# control-board-v0_2_1.net
KiCad netlist of a schematic drawn in EAGLE
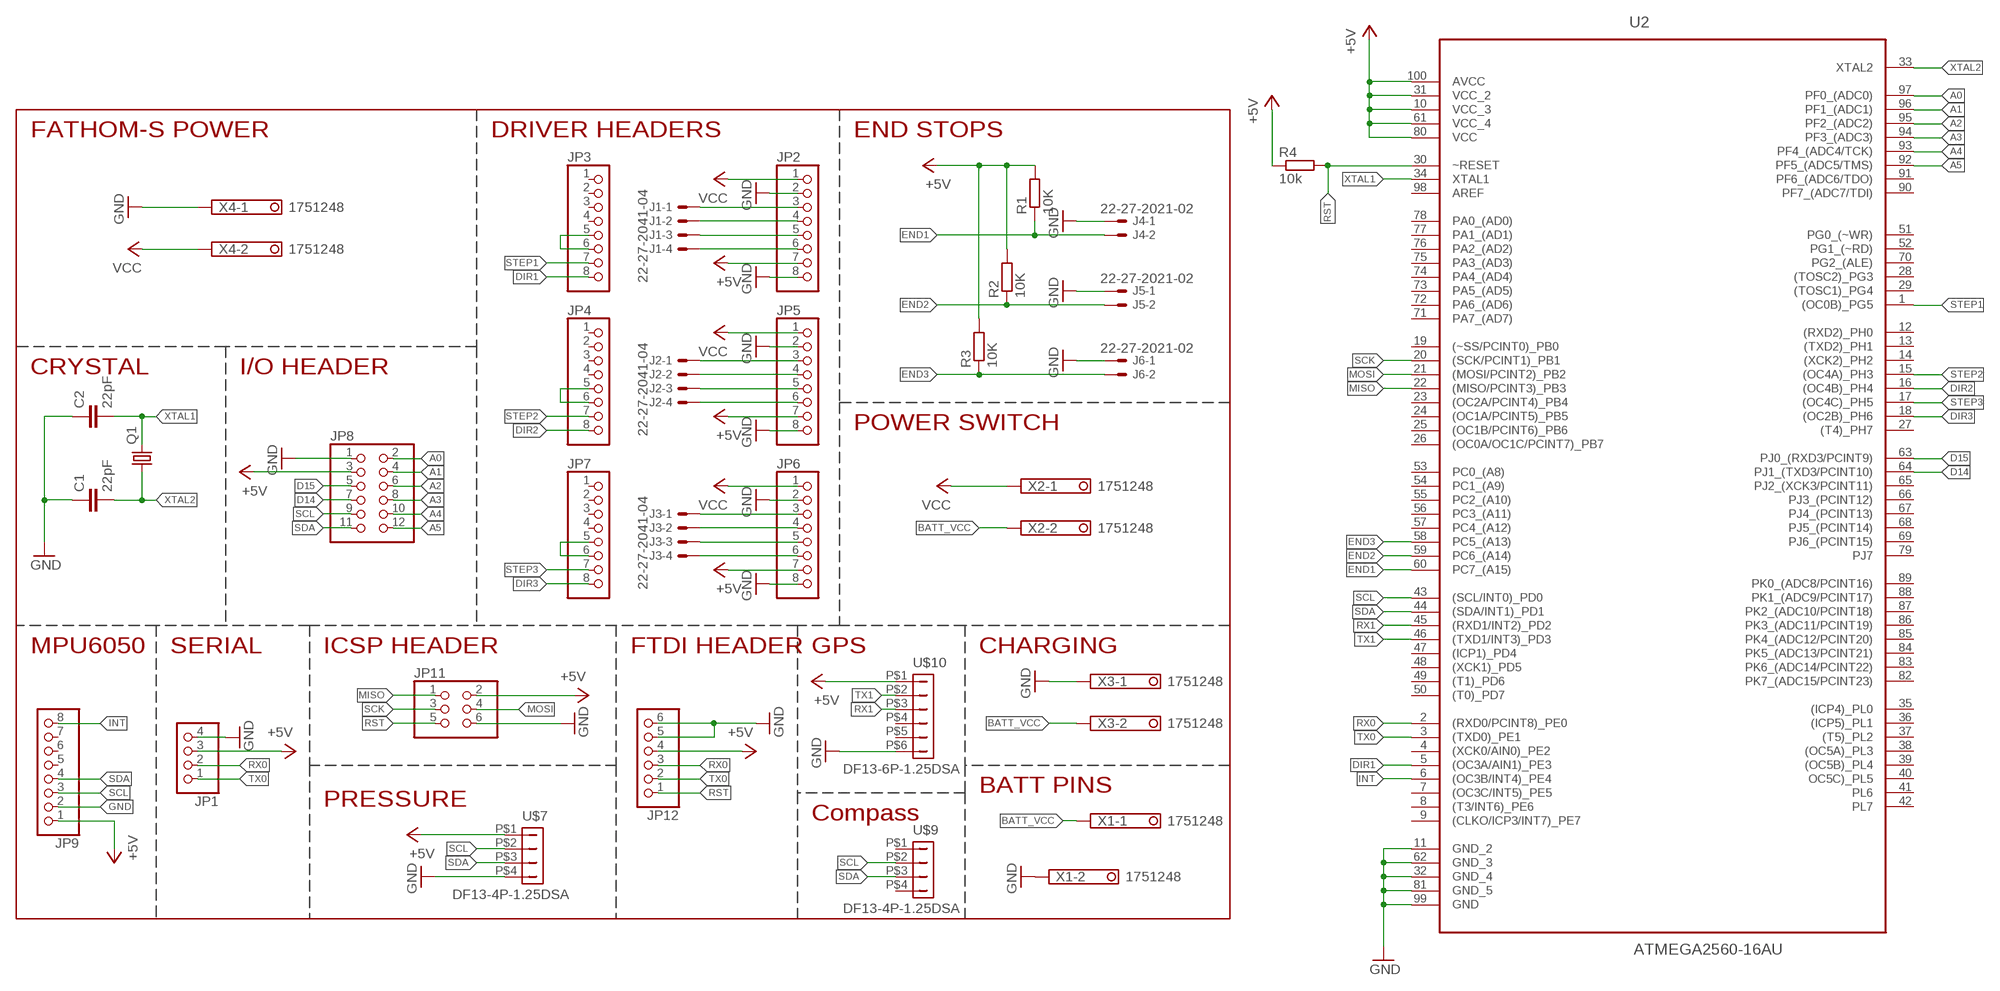
[diagram p0: schematic, sheet 1]

(export (version "E")
  (design (tool "Eeschema 10.0.6"))
  (components
    (comp (ref "C1")
      (value "22pF")
      (footprint "eagle-import:C0603")
      (libsource (lib "eagle-import") (part "C-EUC0603"))
    )
    (comp (ref "C2")
      (value "22pF")
      (footprint "eagle-import:C0603")
      (libsource (lib "eagle-import") (part "C-EUC0603"))
    )
    (comp (ref "J1")
      (value "22-27-2041-04")
      (footprint "eagle-import:6410-04")
      (libsource (lib "eagle-import") (part "22-?-0427-2041"))
    )
    (comp (ref "J2")
      (value "22-27-2041-04")
      (footprint "eagle-import:6410-04")
      (libsource (lib "eagle-import") (part "22-?-0427-2041"))
    )
    (comp (ref "J3")
      (value "22-27-2041-04")
      (footprint "eagle-import:6410-04")
      (libsource (lib "eagle-import") (part "22-?-0427-2041"))
    )
    (comp (ref "J4")
      (value "22-27-2021-02")
      (footprint "eagle-import:6410-02")
      (libsource (lib "eagle-import") (part "22-?-0227-2021"))
    )
    (comp (ref "J5")
      (value "22-27-2021-02")
      (footprint "eagle-import:6410-02")
      (libsource (lib "eagle-import") (part "22-?-0227-2021"))
    )
    (comp (ref "J6")
      (value "22-27-2021-02")
      (footprint "eagle-import:6410-02")
      (libsource (lib "eagle-import") (part "22-?-0227-2021"))
    )
    (comp (ref "JP1")
      (value "PINHD-1X4")
      (footprint "eagle-import:1X04")
      (libsource (lib "eagle-import") (part "PINHD-1X4"))
    )
    (comp (ref "JP2")
      (value "PINHD-1X8")
      (footprint "eagle-import:1X08")
      (libsource (lib "eagle-import") (part "PINHD-1X8"))
    )
    (comp (ref "JP3")
      (value "PINHD-1X8")
      (footprint "eagle-import:1X08")
      (libsource (lib "eagle-import") (part "PINHD-1X8"))
    )
    (comp (ref "JP4")
      (value "PINHD-1X8")
      (footprint "eagle-import:1X08")
      (libsource (lib "eagle-import") (part "PINHD-1X8"))
    )
    (comp (ref "JP5")
      (value "PINHD-1X8")
      (footprint "eagle-import:1X08")
      (libsource (lib "eagle-import") (part "PINHD-1X8"))
    )
    (comp (ref "JP6")
      (value "PINHD-1X8")
      (footprint "eagle-import:1X08")
      (libsource (lib "eagle-import") (part "PINHD-1X8"))
    )
    (comp (ref "JP7")
      (value "PINHD-1X8")
      (footprint "eagle-import:1X08")
      (libsource (lib "eagle-import") (part "PINHD-1X8"))
    )
    (comp (ref "JP8")
      (value "PINHD-2X6")
      (footprint "eagle-import:2X06")
      (libsource (lib "eagle-import") (part "PINHD-2X6"))
    )
    (comp (ref "JP9")
      (value "PINHD-1X8")
      (footprint "eagle-import:1X08")
      (libsource (lib "eagle-import") (part "PINHD-1X8"))
    )
    (comp (ref "JP11")
      (value "PINHD-2X3")
      (footprint "eagle-import:2X03")
      (libsource (lib "eagle-import") (part "PINHD-2X3"))
    )
    (comp (ref "JP12")
      (value "PINHD-1X6")
      (footprint "eagle-import:1X06")
      (libsource (lib "eagle-import") (part "PINHD-1X6"))
    )
    (comp (ref "Q1")
      (value "CRYSTALHC49U70")
      (footprint "eagle-import:HC49U70")
      (libsource (lib "eagle-import") (part "CRYSTALHC49U70"))
    )
    (comp (ref "R1")
      (value "10K")
      (footprint "eagle-import:R0603")
      (libsource (lib "eagle-import") (part "R-EU_R0603"))
    )
    (comp (ref "R2")
      (value "10K")
      (footprint "eagle-import:R0603")
      (libsource (lib "eagle-import") (part "R-EU_R0603"))
    )
    (comp (ref "R3")
      (value "10K")
      (footprint "eagle-import:R0603")
      (libsource (lib "eagle-import") (part "R-EU_R0603"))
    )
    (comp (ref "R4")
      (value "10k")
      (footprint "eagle-import:R0603")
      (libsource (lib "eagle-import") (part "R-EU_R0603"))
    )
    (comp (ref "U$7")
      (value "DF13-4P-1.25DSA")
      (footprint "eagle-import:DF13-4P-1.25DSA")
      (libsource (lib "eagle-import") (part "DF13-4P-1.25DSA"))
    )
    (comp (ref "U$9")
      (value "DF13-4P-1.25DSA")
      (footprint "eagle-import:DF13-4P-1.25DSA")
      (libsource (lib "eagle-import") (part "DF13-4P-1.25DSA"))
    )
    (comp (ref "U$10")
      (value "DF13-6P-1.25DSA")
      (footprint "eagle-import:DF13-6P-1.25DSA")
      (libsource (lib "eagle-import") (part "DF13-6P-1.25DSA"))
    )
    (comp (ref "U2")
      (value "ATMEGA2560-16AU")
      (footprint "eagle-import:QFP50P1600X1600X120-100N")
      (libsource (lib "eagle-import") (part "ATMEGA2560-16AU"))
    )
    (comp (ref "X1")
      (value "1751248")
      (footprint "eagle-import:1751248")
      (libsource (lib "eagle-import") (part "1751248"))
    )
    (comp (ref "X2")
      (value "1751248")
      (footprint "eagle-import:1751248")
      (libsource (lib "eagle-import") (part "1751248"))
    )
    (comp (ref "X3")
      (value "1751248")
      (footprint "eagle-import:1751248")
      (libsource (lib "eagle-import") (part "1751248"))
    )
    (comp (ref "X4")
      (value "1751248")
      (footprint "eagle-import:1751248")
      (libsource (lib "eagle-import") (part "1751248"))
    )
  )
  (nets
    (net (code "1") (name "+5V") (class "Default")
      (node (ref "JP1") (pin "3") (pinfunction "3_3") (pintype "passive"))
      (node (ref "JP11") (pin "2") (pinfunction "2_2") (pintype "passive"))
      (node (ref "JP12") (pin "4") (pinfunction "4_4") (pintype "passive"))
      (node (ref "JP2") (pin "7") (pinfunction "7_7") (pintype "passive"))
      (node (ref "JP5") (pin "7") (pinfunction "7_7") (pintype "passive"))
      (node (ref "JP6") (pin "7") (pinfunction "7_7") (pintype "passive"))
      (node (ref "JP8") (pin "3") (pinfunction "3_3") (pintype "passive"))
      (node (ref "JP9") (pin "1") (pinfunction "1_1") (pintype "passive"))
      (node (ref "R1") (pin "2") (pinfunction "2_2") (pintype "passive"))
      (node (ref "R2") (pin "2") (pinfunction "2_2") (pintype "passive"))
      (node (ref "R3") (pin "2") (pinfunction "2_2") (pintype "passive"))
      (node (ref "R4") (pin "1") (pinfunction "1_1") (pintype "passive"))
      (node (ref "U$10") (pin "P$1") (pinfunction "1_P$1") (pintype "passive"))
      (node (ref "U$7") (pin "P$1") (pinfunction "1_P$1") (pintype "passive"))
      (node (ref "U2") (pin "10") (pinfunction "VCC_3_10") (pintype "power_in"))
      (node (ref "U2") (pin "100") (pinfunction "AVCC_100") (pintype "power_in"))
      (node (ref "U2") (pin "31") (pinfunction "VCC_2_31") (pintype "power_in"))
      (node (ref "U2") (pin "61") (pinfunction "VCC_4_61") (pintype "power_in"))
      (node (ref "U2") (pin "80") (pinfunction "VCC_80") (pintype "power_in"))
    )
    (net (code "2") (name "A0") (class "Default")
      (node (ref "JP8") (pin "2") (pinfunction "2_2") (pintype "passive"))
      (node (ref "U2") (pin "97") (pinfunction "PF0_(ADC0)_97") (pintype "bidirectional"))
    )
    (net (code "3") (name "A1") (class "Default")
      (node (ref "JP8") (pin "4") (pinfunction "4_4") (pintype "passive"))
      (node (ref "U2") (pin "96") (pinfunction "PF1_(ADC1)_96") (pintype "bidirectional"))
    )
    (net (code "4") (name "A2") (class "Default")
      (node (ref "JP8") (pin "6") (pinfunction "6_6") (pintype "passive"))
      (node (ref "U2") (pin "95") (pinfunction "PF2_(ADC2)_95") (pintype "bidirectional"))
    )
    (net (code "5") (name "A3") (class "Default")
      (node (ref "JP8") (pin "8") (pinfunction "8_8") (pintype "passive"))
      (node (ref "U2") (pin "94") (pinfunction "PF3_(ADC3)_94") (pintype "bidirectional"))
    )
    (net (code "6") (name "A4") (class "Default")
      (node (ref "JP8") (pin "10") (pinfunction "10_10") (pintype "passive"))
      (node (ref "U2") (pin "93") (pinfunction "PF4_(ADC4/TCK)_93") (pintype "bidirectional"))
    )
    (net (code "7") (name "A5") (class "Default")
      (node (ref "JP8") (pin "12") (pinfunction "12_12") (pintype "passive"))
      (node (ref "U2") (pin "92") (pinfunction "PF5_(ADC5/TMS)_92") (pintype "bidirectional"))
    )
    (net (code "8") (name "BATT_VCC") (class "Default")
      (node (ref "X1") (pin "1") (pinfunction "K_1") (pintype "passive"))
      (node (ref "X2") (pin "2") (pinfunction "K_2") (pintype "passive"))
      (node (ref "X3") (pin "2") (pinfunction "K_2") (pintype "passive"))
    )
    (net (code "9") (name "D14") (class "Default")
      (node (ref "JP8") (pin "7") (pinfunction "7_7") (pintype "passive"))
      (node (ref "U2") (pin "64") (pinfunction "PJ1_(TXD3/PCINT10)_64") (pintype "bidirectional"))
    )
    (net (code "10") (name "D15") (class "Default")
      (node (ref "JP8") (pin "5") (pinfunction "5_5") (pintype "passive"))
      (node (ref "U2") (pin "63") (pinfunction "PJ0_(RXD3/PCINT9)_63") (pintype "bidirectional"))
    )
    (net (code "11") (name "DIR1") (class "Default")
      (node (ref "JP3") (pin "8") (pinfunction "8_8") (pintype "passive"))
      (node (ref "U2") (pin "5") (pinfunction "(OC3A/AIN1)_PE3_5") (pintype "bidirectional"))
    )
    (net (code "12") (name "DIR2") (class "Default")
      (node (ref "JP4") (pin "8") (pinfunction "8_8") (pintype "passive"))
      (node (ref "U2") (pin "16") (pinfunction "(OC4B)_PH4_16") (pintype "bidirectional"))
    )
    (net (code "13") (name "DIR3") (class "Default")
      (node (ref "JP7") (pin "8") (pinfunction "8_8") (pintype "passive"))
      (node (ref "U2") (pin "18") (pinfunction "(OC2B)_PH6_18") (pintype "bidirectional"))
    )
    (net (code "14") (name "END1") (class "Default")
      (node (ref "J4") (pin "2") (pinfunction "S_2") (pintype "passive"))
      (node (ref "R1") (pin "1") (pinfunction "1_1") (pintype "passive"))
      (node (ref "U2") (pin "60") (pinfunction "PC7_(A15)_60") (pintype "bidirectional"))
    )
    (net (code "15") (name "END2") (class "Default")
      (node (ref "J5") (pin "2") (pinfunction "S_2") (pintype "passive"))
      (node (ref "R2") (pin "1") (pinfunction "1_1") (pintype "passive"))
      (node (ref "U2") (pin "59") (pinfunction "PC6_(A14)_59") (pintype "bidirectional"))
    )
    (net (code "16") (name "END3") (class "Default")
      (node (ref "J6") (pin "2") (pinfunction "S_2") (pintype "passive"))
      (node (ref "R3") (pin "1") (pinfunction "1_1") (pintype "passive"))
      (node (ref "U2") (pin "58") (pinfunction "PC5_(A13)_58") (pintype "bidirectional"))
    )
    (net (code "17") (name "GND") (class "Default")
      (node (ref "C1") (pin "1") (pinfunction "1_1") (pintype "passive"))
      (node (ref "C2") (pin "1") (pinfunction "1_1") (pintype "passive"))
      (node (ref "J4") (pin "1") (pinfunction "S_1") (pintype "passive"))
      (node (ref "J5") (pin "1") (pinfunction "S_1") (pintype "passive"))
      (node (ref "J6") (pin "1") (pinfunction "S_1") (pintype "passive"))
      (node (ref "JP1") (pin "4") (pinfunction "4_4") (pintype "passive"))
      (node (ref "JP11") (pin "6") (pinfunction "6_6") (pintype "passive"))
      (node (ref "JP12") (pin "5") (pinfunction "5_5") (pintype "passive"))
      (node (ref "JP12") (pin "6") (pinfunction "6_6") (pintype "passive"))
      (node (ref "JP2") (pin "2") (pinfunction "2_2") (pintype "passive"))
      (node (ref "JP2") (pin "8") (pinfunction "8_8") (pintype "passive"))
      (node (ref "JP5") (pin "2") (pinfunction "2_2") (pintype "passive"))
      (node (ref "JP5") (pin "8") (pinfunction "8_8") (pintype "passive"))
      (node (ref "JP6") (pin "2") (pinfunction "2_2") (pintype "passive"))
      (node (ref "JP6") (pin "8") (pinfunction "8_8") (pintype "passive"))
      (node (ref "JP8") (pin "1") (pinfunction "1_1") (pintype "passive"))
      (node (ref "JP9") (pin "2") (pinfunction "2_2") (pintype "passive"))
      (node (ref "U$10") (pin "P$6") (pinfunction "6_P$6") (pintype "passive"))
      (node (ref "U$7") (pin "P$4") (pinfunction "4_P$4") (pintype "passive"))
      (node (ref "U2") (pin "11") (pinfunction "GND_2_11") (pintype "passive"))
      (node (ref "U2") (pin "32") (pinfunction "GND_4_32") (pintype "passive"))
      (node (ref "U2") (pin "62") (pinfunction "GND_3_62") (pintype "passive"))
      (node (ref "U2") (pin "81") (pinfunction "GND_5_81") (pintype "passive"))
      (node (ref "U2") (pin "99") (pinfunction "GND_99") (pintype "passive"))
      (node (ref "X1") (pin "2") (pinfunction "K_2") (pintype "passive"))
      (node (ref "X3") (pin "1") (pinfunction "K_1") (pintype "passive"))
      (node (ref "X4") (pin "1") (pinfunction "K_1") (pintype "passive"))
    )
    (net (code "18") (name "INT") (class "Default")
      (node (ref "JP9") (pin "8") (pinfunction "8_8") (pintype "passive"))
      (node (ref "U2") (pin "6") (pinfunction "(OC3B/INT4)_PE4_6") (pintype "bidirectional"))
    )
    (net (code "19") (name "MISO") (class "Default")
      (node (ref "JP11") (pin "1") (pinfunction "1_1") (pintype "passive"))
      (node (ref "U2") (pin "22") (pinfunction "(MISO/PCINT3)_PB3_22") (pintype "bidirectional"))
    )
    (net (code "20") (name "MOSI") (class "Default")
      (node (ref "JP11") (pin "4") (pinfunction "4_4") (pintype "passive"))
      (node (ref "U2") (pin "21") (pinfunction "(MOSI/PCINT2)_PB2_21") (pintype "bidirectional"))
    )
    (net (code "21") (name "Net-(J1A-S)") (class "Default")
      (node (ref "J1") (pin "1") (pinfunction "S_1") (pintype "passive"))
      (node (ref "JP2") (pin "3") (pinfunction "3_3") (pintype "passive"))
    )
    (net (code "22") (name "Net-(J1B-S)") (class "Default")
      (node (ref "J1") (pin "2") (pinfunction "S_2") (pintype "passive"))
      (node (ref "JP2") (pin "4") (pinfunction "4_4") (pintype "passive"))
    )
    (net (code "23") (name "Net-(J1C-S)") (class "Default")
      (node (ref "J1") (pin "3") (pinfunction "S_3") (pintype "passive"))
      (node (ref "JP2") (pin "5") (pinfunction "5_5") (pintype "passive"))
    )
    (net (code "24") (name "Net-(J1D-S)") (class "Default")
      (node (ref "J1") (pin "4") (pinfunction "S_4") (pintype "passive"))
      (node (ref "JP2") (pin "6") (pinfunction "6_6") (pintype "passive"))
    )
    (net (code "25") (name "Net-(J2A-S)") (class "Default")
      (node (ref "J2") (pin "1") (pinfunction "S_1") (pintype "passive"))
      (node (ref "JP5") (pin "3") (pinfunction "3_3") (pintype "passive"))
    )
    (net (code "26") (name "Net-(J2B-S)") (class "Default")
      (node (ref "J2") (pin "2") (pinfunction "S_2") (pintype "passive"))
      (node (ref "JP5") (pin "4") (pinfunction "4_4") (pintype "passive"))
    )
    (net (code "27") (name "Net-(J2C-S)") (class "Default")
      (node (ref "J2") (pin "3") (pinfunction "S_3") (pintype "passive"))
      (node (ref "JP5") (pin "5") (pinfunction "5_5") (pintype "passive"))
    )
    (net (code "28") (name "Net-(J2D-S)") (class "Default")
      (node (ref "J2") (pin "4") (pinfunction "S_4") (pintype "passive"))
      (node (ref "JP5") (pin "6") (pinfunction "6_6") (pintype "passive"))
    )
    (net (code "29") (name "Net-(J3A-S)") (class "Default")
      (node (ref "J3") (pin "1") (pinfunction "S_1") (pintype "passive"))
      (node (ref "JP6") (pin "3") (pinfunction "3_3") (pintype "passive"))
    )
    (net (code "30") (name "Net-(J3B-S)") (class "Default")
      (node (ref "J3") (pin "2") (pinfunction "S_2") (pintype "passive"))
      (node (ref "JP6") (pin "4") (pinfunction "4_4") (pintype "passive"))
    )
    (net (code "31") (name "Net-(J3C-S)") (class "Default")
      (node (ref "J3") (pin "3") (pinfunction "S_3") (pintype "passive"))
      (node (ref "JP6") (pin "5") (pinfunction "5_5") (pintype "passive"))
    )
    (net (code "32") (name "Net-(J3D-S)") (class "Default")
      (node (ref "J3") (pin "4") (pinfunction "S_4") (pintype "passive"))
      (node (ref "JP6") (pin "6") (pinfunction "6_6") (pintype "passive"))
    )
    (net (code "33") (name "Net-(JP3-Pad5)") (class "Default")
      (node (ref "JP3") (pin "5") (pinfunction "5_5") (pintype "passive"))
      (node (ref "JP3") (pin "6") (pinfunction "6_6") (pintype "passive"))
    )
    (net (code "34") (name "Net-(JP4-Pad5)") (class "Default")
      (node (ref "JP4") (pin "5") (pinfunction "5_5") (pintype "passive"))
      (node (ref "JP4") (pin "6") (pinfunction "6_6") (pintype "passive"))
    )
    (net (code "35") (name "Net-(JP7-Pad5)") (class "Default")
      (node (ref "JP7") (pin "5") (pinfunction "5_5") (pintype "passive"))
      (node (ref "JP7") (pin "6") (pinfunction "6_6") (pintype "passive"))
    )
    (net (code "36") (name "RST") (class "Default")
      (node (ref "JP11") (pin "5") (pinfunction "5_5") (pintype "passive"))
      (node (ref "JP12") (pin "1") (pinfunction "1_1") (pintype "passive"))
      (node (ref "R4") (pin "2") (pinfunction "2_2") (pintype "passive"))
      (node (ref "U2") (pin "30") (pinfunction "~{RESET}_30") (pintype "input"))
    )
    (net (code "37") (name "RX0") (class "Default")
      (node (ref "JP1") (pin "2") (pinfunction "2_2") (pintype "passive"))
      (node (ref "JP12") (pin "3") (pinfunction "3_3") (pintype "passive"))
      (node (ref "U2") (pin "2") (pinfunction "(RXD0/PCINT8)_PE0_2") (pintype "bidirectional"))
    )
    (net (code "38") (name "RX1") (class "Default")
      (node (ref "U$10") (pin "P$3") (pinfunction "3_P$3") (pintype "passive"))
      (node (ref "U2") (pin "45") (pinfunction "(RXD1/INT2)_PD2_45") (pintype "bidirectional"))
    )
    (net (code "39") (name "SCK") (class "Default")
      (node (ref "JP11") (pin "3") (pinfunction "3_3") (pintype "passive"))
      (node (ref "U2") (pin "20") (pinfunction "(SCK/PCINT1)_PB1_20") (pintype "bidirectional"))
    )
    (net (code "40") (name "SCL") (class "Default")
      (node (ref "JP8") (pin "9") (pinfunction "9_9") (pintype "passive"))
      (node (ref "JP9") (pin "3") (pinfunction "3_3") (pintype "passive"))
      (node (ref "U$7") (pin "P$2") (pinfunction "2_P$2") (pintype "passive"))
      (node (ref "U$9") (pin "P$2") (pinfunction "2_P$2") (pintype "passive"))
      (node (ref "U2") (pin "43") (pinfunction "(SCL/INT0)_PD0_43") (pintype "bidirectional"))
    )
    (net (code "41") (name "SDA") (class "Default")
      (node (ref "JP8") (pin "11") (pinfunction "11_11") (pintype "passive"))
      (node (ref "JP9") (pin "4") (pinfunction "4_4") (pintype "passive"))
      (node (ref "U$7") (pin "P$3") (pinfunction "3_P$3") (pintype "passive"))
      (node (ref "U$9") (pin "P$3") (pinfunction "3_P$3") (pintype "passive"))
      (node (ref "U2") (pin "44") (pinfunction "(SDA/INT1)_PD1_44") (pintype "bidirectional"))
    )
    (net (code "42") (name "STEP1") (class "Default")
      (node (ref "JP3") (pin "7") (pinfunction "7_7") (pintype "passive"))
      (node (ref "U2") (pin "1") (pinfunction "(OC0B)_PG5_1") (pintype "bidirectional"))
    )
    (net (code "43") (name "STEP2") (class "Default")
      (node (ref "JP4") (pin "7") (pinfunction "7_7") (pintype "passive"))
      (node (ref "U2") (pin "15") (pinfunction "(OC4A)_PH3_15") (pintype "bidirectional"))
    )
    (net (code "44") (name "STEP3") (class "Default")
      (node (ref "JP7") (pin "7") (pinfunction "7_7") (pintype "passive"))
      (node (ref "U2") (pin "17") (pinfunction "(OC4C)_PH5_17") (pintype "bidirectional"))
    )
    (net (code "45") (name "TX0") (class "Default")
      (node (ref "JP1") (pin "1") (pinfunction "1_1") (pintype "passive"))
      (node (ref "JP12") (pin "2") (pinfunction "2_2") (pintype "passive"))
      (node (ref "U2") (pin "3") (pinfunction "(TXD0)_PE1_3") (pintype "bidirectional"))
    )
    (net (code "46") (name "TX1") (class "Default")
      (node (ref "U$10") (pin "P$2") (pinfunction "2_P$2") (pintype "passive"))
      (node (ref "U2") (pin "46") (pinfunction "(TXD1/INT3)_PD3_46") (pintype "bidirectional"))
    )
    (net (code "47") (name "VCC") (class "Default")
      (node (ref "JP2") (pin "1") (pinfunction "1_1") (pintype "passive"))
      (node (ref "JP5") (pin "1") (pinfunction "1_1") (pintype "passive"))
      (node (ref "JP6") (pin "1") (pinfunction "1_1") (pintype "passive"))
      (node (ref "X2") (pin "1") (pinfunction "K_1") (pintype "passive"))
      (node (ref "X4") (pin "2") (pinfunction "K_2") (pintype "passive"))
    )
    (net (code "48") (name "XTAL1") (class "Default")
      (node (ref "C2") (pin "2") (pinfunction "2_2") (pintype "passive"))
      (node (ref "Q1") (pin "2") (pinfunction "2_2") (pintype "passive"))
      (node (ref "U2") (pin "34") (pinfunction "XTAL1_34") (pintype "input"))
    )
    (net (code "49") (name "XTAL2") (class "Default")
      (node (ref "C1") (pin "2") (pinfunction "2_2") (pintype "passive"))
      (node (ref "Q1") (pin "1") (pinfunction "1_1") (pintype "passive"))
      (node (ref "U2") (pin "33") (pinfunction "XTAL2_33") (pintype "output"))
    )
    (net (code "50") (name "unconnected-(JP3-Pad1)") (class "Default")
      (node (ref "JP3") (pin "1") (pinfunction "1_1") (pintype "passive"))
    )
    (net (code "51") (name "unconnected-(JP3-Pad2)") (class "Default")
      (node (ref "JP3") (pin "2") (pinfunction "2_2") (pintype "passive"))
    )
    (net (code "52") (name "unconnected-(JP3-Pad3)") (class "Default")
      (node (ref "JP3") (pin "3") (pinfunction "3_3") (pintype "passive"))
    )
    (net (code "53") (name "unconnected-(JP3-Pad4)") (class "Default")
      (node (ref "JP3") (pin "4") (pinfunction "4_4") (pintype "passive"))
    )
    (net (code "54") (name "unconnected-(JP4-Pad1)") (class "Default")
      (node (ref "JP4") (pin "1") (pinfunction "1_1") (pintype "passive"))
    )
    (net (code "55") (name "unconnected-(JP4-Pad2)") (class "Default")
      (node (ref "JP4") (pin "2") (pinfunction "2_2") (pintype "passive"))
    )
    (net (code "56") (name "unconnected-(JP4-Pad3)") (class "Default")
      (node (ref "JP4") (pin "3") (pinfunction "3_3") (pintype "passive"))
    )
    (net (code "57") (name "unconnected-(JP4-Pad4)") (class "Default")
      (node (ref "JP4") (pin "4") (pinfunction "4_4") (pintype "passive"))
    )
    (net (code "58") (name "unconnected-(JP7-Pad1)") (class "Default")
      (node (ref "JP7") (pin "1") (pinfunction "1_1") (pintype "passive"))
    )
    (net (code "59") (name "unconnected-(JP7-Pad2)") (class "Default")
      (node (ref "JP7") (pin "2") (pinfunction "2_2") (pintype "passive"))
    )
    (net (code "60") (name "unconnected-(JP7-Pad3)") (class "Default")
      (node (ref "JP7") (pin "3") (pinfunction "3_3") (pintype "passive"))
    )
    (net (code "61") (name "unconnected-(JP7-Pad4)") (class "Default")
      (node (ref "JP7") (pin "4") (pinfunction "4_4") (pintype "passive"))
    )
    (net (code "62") (name "unconnected-(JP9-Pad5)") (class "Default")
      (node (ref "JP9") (pin "5") (pinfunction "5_5") (pintype "passive"))
    )
    (net (code "63") (name "unconnected-(JP9-Pad6)") (class "Default")
      (node (ref "JP9") (pin "6") (pinfunction "6_6") (pintype "passive"))
    )
    (net (code "64") (name "unconnected-(JP9-Pad7)") (class "Default")
      (node (ref "JP9") (pin "7") (pinfunction "7_7") (pintype "passive"))
    )
    (net (code "65") (name "unconnected-(U$9-1-PadP$1)") (class "Default")
      (node (ref "U$9") (pin "P$1") (pinfunction "1_P$1") (pintype "passive"))
    )
    (net (code "66") (name "unconnected-(U$9-4-PadP$4)") (class "Default")
      (node (ref "U$9") (pin "P$4") (pinfunction "4_P$4") (pintype "passive"))
    )
    (net (code "67") (name "unconnected-(U$10-4-PadP$4)") (class "Default")
      (node (ref "U$10") (pin "P$4") (pinfunction "4_P$4") (pintype "passive"))
    )
    (net (code "68") (name "unconnected-(U$10-5-PadP$5)") (class "Default")
      (node (ref "U$10") (pin "P$5") (pinfunction "5_P$5") (pintype "passive"))
    )
    (net (code "69") (name "unconnected-(U2-(CLKO{slash}ICP3{slash}INT7)_PE7-Pad9)") (class "Default")
      (node (ref "U2") (pin "9") (pinfunction "(CLKO/ICP3/INT7)_PE7_9") (pintype "bidirectional"))
    )
    (net (code "70") (name "unconnected-(U2-(ICP1)_PD4-Pad47)") (class "Default")
      (node (ref "U2") (pin "47") (pinfunction "(ICP1)_PD4_47") (pintype "bidirectional"))
    )
    (net (code "71") (name "unconnected-(U2-(ICP4)_PL0-Pad35)") (class "Default")
      (node (ref "U2") (pin "35") (pinfunction "(ICP4)_PL0_35") (pintype "bidirectional"))
    )
    (net (code "72") (name "unconnected-(U2-(ICP5)_PL1-Pad36)") (class "Default")
      (node (ref "U2") (pin "36") (pinfunction "(ICP5)_PL1_36") (pintype "bidirectional"))
    )
    (net (code "73") (name "unconnected-(U2-(OC0A{slash}OC1C{slash}PCINT7)_PB7-Pad26)") (class "Default")
      (node (ref "U2") (pin "26") (pinfunction "(OC0A/OC1C/PCINT7)_PB7_26") (pintype "bidirectional"))
    )
    (net (code "74") (name "unconnected-(U2-(OC1A{slash}PCINT5)_PB5-Pad24)") (class "Default")
      (node (ref "U2") (pin "24") (pinfunction "(OC1A/PCINT5)_PB5_24") (pintype "bidirectional"))
    )
    (net (code "75") (name "unconnected-(U2-(OC1B{slash}PCINT6)_PB6-Pad25)") (class "Default")
      (node (ref "U2") (pin "25") (pinfunction "(OC1B/PCINT6)_PB6_25") (pintype "bidirectional"))
    )
    (net (code "76") (name "unconnected-(U2-(OC2A{slash}PCINT4)_PB4-Pad23)") (class "Default")
      (node (ref "U2") (pin "23") (pinfunction "(OC2A/PCINT4)_PB4_23") (pintype "bidirectional"))
    )
    (net (code "77") (name "unconnected-(U2-(OC3C{slash}INT5)_PE5-Pad7)") (class "Default")
      (node (ref "U2") (pin "7") (pinfunction "(OC3C/INT5)_PE5_7") (pintype "bidirectional"))
    )
    (net (code "78") (name "unconnected-(U2-(OC5A)_PL3-Pad38)") (class "Default")
      (node (ref "U2") (pin "38") (pinfunction "(OC5A)_PL3_38") (pintype "bidirectional"))
    )
    (net (code "79") (name "unconnected-(U2-(OC5B)_PL4-Pad39)") (class "Default")
      (node (ref "U2") (pin "39") (pinfunction "(OC5B)_PL4_39") (pintype "bidirectional"))
    )
    (net (code "80") (name "unconnected-(U2-(RXD2)_PH0-Pad12)") (class "Default")
      (node (ref "U2") (pin "12") (pinfunction "(RXD2)_PH0_12") (pintype "bidirectional"))
    )
    (net (code "81") (name "unconnected-(U2-(T0)_PD7-Pad50)") (class "Default")
      (node (ref "U2") (pin "50") (pinfunction "(T0)_PD7_50") (pintype "bidirectional"))
    )
    (net (code "82") (name "unconnected-(U2-(T1)_PD6-Pad49)") (class "Default")
      (node (ref "U2") (pin "49") (pinfunction "(T1)_PD6_49") (pintype "bidirectional"))
    )
    (net (code "83") (name "unconnected-(U2-(T3{slash}INT6)_PE6-Pad8)") (class "Default")
      (node (ref "U2") (pin "8") (pinfunction "(T3/INT6)_PE6_8") (pintype "bidirectional"))
    )
    (net (code "84") (name "unconnected-(U2-(T4)_PH7-Pad27)") (class "Default")
      (node (ref "U2") (pin "27") (pinfunction "(T4)_PH7_27") (pintype "bidirectional"))
    )
    (net (code "85") (name "unconnected-(U2-(T5)_PL2-Pad37)") (class "Default")
      (node (ref "U2") (pin "37") (pinfunction "(T5)_PL2_37") (pintype "bidirectional"))
    )
    (net (code "86") (name "unconnected-(U2-(TOSC1)_PG4-Pad29)") (class "Default")
      (node (ref "U2") (pin "29") (pinfunction "(TOSC1)_PG4_29") (pintype "bidirectional"))
    )
    (net (code "87") (name "unconnected-(U2-(TOSC2)_PG3-Pad28)") (class "Default")
      (node (ref "U2") (pin "28") (pinfunction "(TOSC2)_PG3_28") (pintype "bidirectional"))
    )
    (net (code "88") (name "unconnected-(U2-(TXD2)_PH1-Pad13)") (class "Default")
      (node (ref "U2") (pin "13") (pinfunction "(TXD2)_PH1_13") (pintype "bidirectional"))
    )
    (net (code "89") (name "unconnected-(U2-(XCK0{slash}AIN0)_PE2-Pad4)") (class "Default")
      (node (ref "U2") (pin "4") (pinfunction "(XCK0/AIN0)_PE2_4") (pintype "bidirectional"))
    )
    (net (code "90") (name "unconnected-(U2-(XCK1)_PD5-Pad48)") (class "Default")
      (node (ref "U2") (pin "48") (pinfunction "(XCK1)_PD5_48") (pintype "bidirectional"))
    )
    (net (code "91") (name "unconnected-(U2-(XCK2)_PH2-Pad14)") (class "Default")
      (node (ref "U2") (pin "14") (pinfunction "(XCK2)_PH2_14") (pintype "bidirectional"))
    )
    (net (code "92") (name "unconnected-(U2-(~{SS{slash}PCINT0})_PB0-Pad19)") (class "Default")
      (node (ref "U2") (pin "19") (pinfunction "(~{SS/PCINT0})_PB0_19") (pintype "bidirectional"))
    )
    (net (code "93") (name "unconnected-(U2-AREF-Pad98)") (class "Default")
      (node (ref "U2") (pin "98") (pinfunction "AREF_98") (pintype "input"))
    )
    (net (code "94") (name "unconnected-(U2-OC5C)_PL5-Pad40)") (class "Default")
      (node (ref "U2") (pin "40") (pinfunction "OC5C)_PL5_40") (pintype "bidirectional"))
    )
    (net (code "95") (name "unconnected-(U2-PA0_(AD0)-Pad78)") (class "Default")
      (node (ref "U2") (pin "78") (pinfunction "PA0_(AD0)_78") (pintype "bidirectional"))
    )
    (net (code "96") (name "unconnected-(U2-PA1_(AD1)-Pad77)") (class "Default")
      (node (ref "U2") (pin "77") (pinfunction "PA1_(AD1)_77") (pintype "bidirectional"))
    )
    (net (code "97") (name "unconnected-(U2-PA2_(AD2)-Pad76)") (class "Default")
      (node (ref "U2") (pin "76") (pinfunction "PA2_(AD2)_76") (pintype "bidirectional"))
    )
    (net (code "98") (name "unconnected-(U2-PA3_(AD3)-Pad75)") (class "Default")
      (node (ref "U2") (pin "75") (pinfunction "PA3_(AD3)_75") (pintype "bidirectional"))
    )
    (net (code "99") (name "unconnected-(U2-PA4_(AD4)-Pad74)") (class "Default")
      (node (ref "U2") (pin "74") (pinfunction "PA4_(AD4)_74") (pintype "bidirectional"))
    )
    (net (code "100") (name "unconnected-(U2-PA5_(AD5)-Pad73)") (class "Default")
      (node (ref "U2") (pin "73") (pinfunction "PA5_(AD5)_73") (pintype "bidirectional"))
    )
    (net (code "101") (name "unconnected-(U2-PA6_(AD6)-Pad72)") (class "Default")
      (node (ref "U2") (pin "72") (pinfunction "PA6_(AD6)_72") (pintype "bidirectional"))
    )
    (net (code "102") (name "unconnected-(U2-PA7_(AD7)-Pad71)") (class "Default")
      (node (ref "U2") (pin "71") (pinfunction "PA7_(AD7)_71") (pintype "bidirectional"))
    )
    (net (code "103") (name "unconnected-(U2-PC0_(A8)-Pad53)") (class "Default")
      (node (ref "U2") (pin "53") (pinfunction "PC0_(A8)_53") (pintype "bidirectional"))
    )
    (net (code "104") (name "unconnected-(U2-PC1_(A9)-Pad54)") (class "Default")
      (node (ref "U2") (pin "54") (pinfunction "PC1_(A9)_54") (pintype "bidirectional"))
    )
    (net (code "105") (name "unconnected-(U2-PC2_(A10)-Pad55)") (class "Default")
      (node (ref "U2") (pin "55") (pinfunction "PC2_(A10)_55") (pintype "bidirectional"))
    )
    (net (code "106") (name "unconnected-(U2-PC3_(A11)-Pad56)") (class "Default")
      (node (ref "U2") (pin "56") (pinfunction "PC3_(A11)_56") (pintype "bidirectional"))
    )
    (net (code "107") (name "unconnected-(U2-PC4_(A12)-Pad57)") (class "Default")
      (node (ref "U2") (pin "57") (pinfunction "PC4_(A12)_57") (pintype "bidirectional"))
    )
    (net (code "108") (name "unconnected-(U2-PF6_(ADC6{slash}TDO)-Pad91)") (class "Default")
      (node (ref "U2") (pin "91") (pinfunction "PF6_(ADC6/TDO)_91") (pintype "bidirectional"))
    )
    (net (code "109") (name "unconnected-(U2-PF7_(ADC7{slash}TDI)-Pad90)") (class "Default")
      (node (ref "U2") (pin "90") (pinfunction "PF7_(ADC7/TDI)_90") (pintype "bidirectional"))
    )
    (net (code "110") (name "unconnected-(U2-PG0_(~{WR})-Pad51)") (class "Default")
      (node (ref "U2") (pin "51") (pinfunction "PG0_(~{WR})_51") (pintype "bidirectional"))
    )
    (net (code "111") (name "unconnected-(U2-PG1_(~{RD})-Pad52)") (class "Default")
      (node (ref "U2") (pin "52") (pinfunction "PG1_(~{RD})_52") (pintype "bidirectional"))
    )
    (net (code "112") (name "unconnected-(U2-PG2_(ALE)-Pad70)") (class "Default")
      (node (ref "U2") (pin "70") (pinfunction "PG2_(ALE)_70") (pintype "bidirectional"))
    )
    (net (code "113") (name "unconnected-(U2-PJ2_(XCK3{slash}PCINT11)-Pad65)") (class "Default")
      (node (ref "U2") (pin "65") (pinfunction "PJ2_(XCK3/PCINT11)_65") (pintype "bidirectional"))
    )
    (net (code "114") (name "unconnected-(U2-PJ3_(PCINT12)-Pad66)") (class "Default")
      (node (ref "U2") (pin "66") (pinfunction "PJ3_(PCINT12)_66") (pintype "bidirectional"))
    )
    (net (code "115") (name "unconnected-(U2-PJ4_(PCINT13)-Pad67)") (class "Default")
      (node (ref "U2") (pin "67") (pinfunction "PJ4_(PCINT13)_67") (pintype "bidirectional"))
    )
    (net (code "116") (name "unconnected-(U2-PJ5_(PCINT14)-Pad68)") (class "Default")
      (node (ref "U2") (pin "68") (pinfunction "PJ5_(PCINT14)_68") (pintype "bidirectional"))
    )
    (net (code "117") (name "unconnected-(U2-PJ6_(PCINT15)-Pad69)") (class "Default")
      (node (ref "U2") (pin "69") (pinfunction "PJ6_(PCINT15)_69") (pintype "bidirectional"))
    )
    (net (code "118") (name "unconnected-(U2-PJ7-Pad79)") (class "Default")
      (node (ref "U2") (pin "79") (pinfunction "PJ7_79") (pintype "bidirectional"))
    )
    (net (code "119") (name "unconnected-(U2-PK0_(ADC8{slash}PCINT16)-Pad89)") (class "Default")
      (node (ref "U2") (pin "89") (pinfunction "PK0_(ADC8/PCINT16)_89") (pintype "bidirectional"))
    )
    (net (code "120") (name "unconnected-(U2-PK1_(ADC9{slash}PCINT17)-Pad88)") (class "Default")
      (node (ref "U2") (pin "88") (pinfunction "PK1_(ADC9/PCINT17)_88") (pintype "bidirectional"))
    )
    (net (code "121") (name "unconnected-(U2-PK2_(ADC10{slash}PCINT18)-Pad87)") (class "Default")
      (node (ref "U2") (pin "87") (pinfunction "PK2_(ADC10/PCINT18)_87") (pintype "bidirectional"))
    )
    (net (code "122") (name "unconnected-(U2-PK3_(ADC11{slash}PCINT19)-Pad86)") (class "Default")
      (node (ref "U2") (pin "86") (pinfunction "PK3_(ADC11/PCINT19)_86") (pintype "bidirectional"))
    )
    (net (code "123") (name "unconnected-(U2-PK4_(ADC12{slash}PCINT20)-Pad85)") (class "Default")
      (node (ref "U2") (pin "85") (pinfunction "PK4_(ADC12/PCINT20)_85") (pintype "bidirectional"))
    )
    (net (code "124") (name "unconnected-(U2-PK5_(ADC13{slash}PCINT21)-Pad84)") (class "Default")
      (node (ref "U2") (pin "84") (pinfunction "PK5_(ADC13/PCINT21)_84") (pintype "bidirectional"))
    )
    (net (code "125") (name "unconnected-(U2-PK6_(ADC14{slash}PCINT22)-Pad83)") (class "Default")
      (node (ref "U2") (pin "83") (pinfunction "PK6_(ADC14/PCINT22)_83") (pintype "bidirectional"))
    )
    (net (code "126") (name "unconnected-(U2-PK7_(ADC15{slash}PCINT23)-Pad82)") (class "Default")
      (node (ref "U2") (pin "82") (pinfunction "PK7_(ADC15/PCINT23)_82") (pintype "bidirectional"))
    )
    (net (code "127") (name "unconnected-(U2-PL6-Pad41)") (class "Default")
      (node (ref "U2") (pin "41") (pinfunction "PL6_41") (pintype "bidirectional"))
    )
    (net (code "128") (name "unconnected-(U2-PL7-Pad42)") (class "Default")
      (node (ref "U2") (pin "42") (pinfunction "PL7_42") (pintype "bidirectional"))
    )
  )
)
